# USB_PWR_SWITCH_DUAL_AP2152.net
KiCad netlist of a schematic drawn in Altium Designer
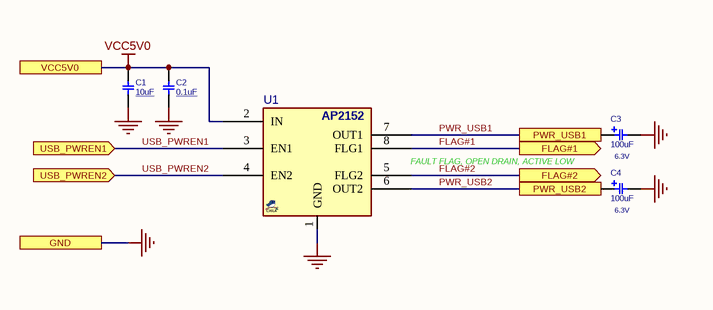
[diagram p0: USB_PWR_SWITCH_DUAL_AP2152.SchDoc]

(export (version "E")
  (design (tool "Eeschema 10.0.6"))
  (components
    (comp (ref "C1")
      (value "10uF")
      (footprint "C0603")
      (description "CAP, MLCC")
      (fields (field (name "MANF_P#") "CL05A106MP5NUNC") (field (name "MANF") "Samsung"))
      (libsource (lib "mlcc_smd_passive") (part "CAP_SMD_MLCC"))
    )
    (comp (ref "C2")
      (value "0.1uF")
      (footprint "C0402")
      (description "CAP, MLCC")
      (fields (field (name "MANF_P#") "GRM155R61E104") (field (name "MANF") "Murata"))
      (libsource (lib "mlcc_smd_passive") (part "CAP_SMD_MLCC"))
    )
    (comp (ref "C3")
      (value "100uF")
      (footprint "C_TN_3528")
      (description "CAP, SMD, TAN,")
      (fields (field (name "PARAM2") "6.3V"))
      (libsource (lib "passive_smd") (part "CAP_SMD_TAN_3528"))
    )
    (comp (ref "C4")
      (value "100uF")
      (footprint "C_TN_3528")
      (description "CAP, SMD, TAN,")
      (fields (field (name "PARAM2") "6.3V"))
      (libsource (lib "passive_smd") (part "CAP_SMD_TAN_3528"))
    )
    (comp (ref "U1")
      (value "AP2152")
      (footprint "SO_8")
      (description "LOAD SW, Dual Port USB, Over-Current Protection")
      (fields (field (name "MANF") "Diodes") (field (name "MANF_P#") "AP2152SG-13"))
      (libsource (lib "power_load_switch") (part "AP2152_SOP8"))
    )
  )
  (nets
    (net (code "1") (name "/FLAG#1") (class "Default")
      (node (ref "U1") (pin "8") (pinfunction "FLG1_8") (pintype "passive"))
    )
    (net (code "2") (name "/FLAG#2") (class "Default")
      (node (ref "U1") (pin "5") (pinfunction "FLG2_5") (pintype "passive"))
    )
    (net (code "3") (name "/PWR_USB1") (class "Default")
      (node (ref "C3") (pin "1") (pinfunction "1_1") (pintype "passive"))
      (node (ref "U1") (pin "7") (pinfunction "OUT1_7") (pintype "passive"))
    )
    (net (code "4") (name "/PWR_USB2") (class "Default")
      (node (ref "C4") (pin "1") (pinfunction "1_1") (pintype "passive"))
      (node (ref "U1") (pin "6") (pinfunction "OUT2_6") (pintype "passive"))
    )
    (net (code "5") (name "/USB_PWREN1") (class "Default")
      (node (ref "U1") (pin "3") (pinfunction "EN1_3") (pintype "passive"))
    )
    (net (code "6") (name "/USB_PWREN2") (class "Default")
      (node (ref "U1") (pin "4") (pinfunction "EN2_4") (pintype "passive"))
    )
    (net (code "7") (name "GND") (class "Default")
      (node (ref "C1") (pin "2") (pinfunction "2_2") (pintype "passive"))
      (node (ref "C2") (pin "2") (pinfunction "2_2") (pintype "passive"))
      (node (ref "C3") (pin "2") (pinfunction "2_2") (pintype "passive"))
      (node (ref "C4") (pin "2") (pinfunction "2_2") (pintype "passive"))
      (node (ref "U1") (pin "1") (pinfunction "GND_1") (pintype "passive"))
    )
    (net (code "8") (name "VCC5V0") (class "Default")
      (node (ref "C1") (pin "1") (pinfunction "1_1") (pintype "passive"))
      (node (ref "C2") (pin "1") (pinfunction "1_1") (pintype "passive"))
      (node (ref "U1") (pin "2") (pinfunction "IN_2") (pintype "passive"))
    )
  )
)
